# FrontEnd.net
KiCad netlist of a schematic drawn in EAGLE
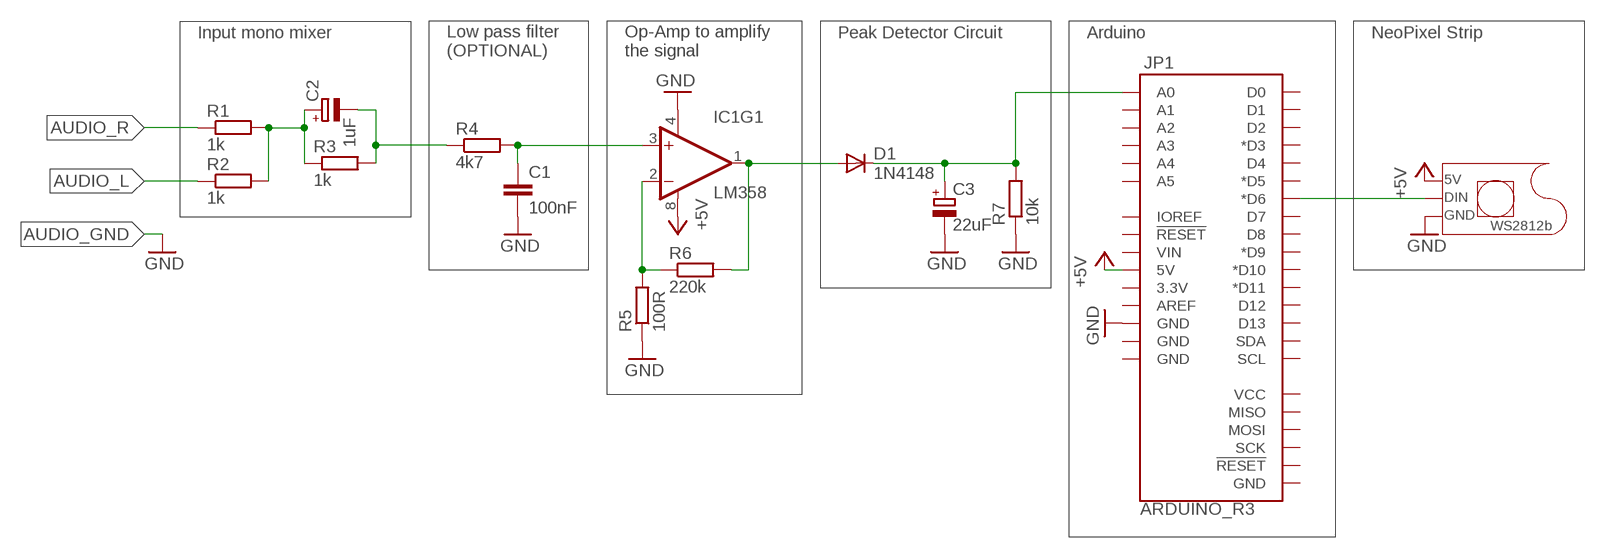
[diagram p0: schematic, sheet 1]

(export (version "E")
  (design (tool "Eeschema 10.0.6"))
  (components
    (comp (ref "C1")
      (value "100nF")
      (footprint "eagle-import:C025-024X044")
      (libsource (lib "eagle-import") (part "C-EU025-024X044"))
    )
    (comp (ref "C2")
      (value "1uF")
      (footprint "eagle-import:085CS_1AR")
      (libsource (lib "eagle-import") (part "CPOL-EU085CS-1AR"))
    )
    (comp (ref "C3")
      (value "22uF")
      (footprint "eagle-import:085CS_1AR")
      (libsource (lib "eagle-import") (part "CPOL-EU085CS-1AR"))
    )
    (comp (ref "D1")
      (value "1N4148")
      (footprint "eagle-import:DO35-10")
      (libsource (lib "eagle-import") (part "1N4148DO35-10"))
    )
    (comp (ref "IC1")
      (value "LM358")
      (footprint "eagle-import:DIP08")
      (libsource (lib "eagle-import") (part "LM358"))
    )
    (comp (ref "JP1")
      (value "ARDUINO_R3")
      (footprint "eagle-import:ARDUINO_R3")
      (libsource (lib "eagle-import") (part "ARDUINO_R3"))
    )
    (comp (ref "R1")
      (value "1k")
      (footprint "eagle-import:0204V")
      (libsource (lib "eagle-import") (part "R-EU_0204/2V"))
    )
    (comp (ref "R2")
      (value "1k")
      (footprint "eagle-import:0204V")
      (libsource (lib "eagle-import") (part "R-EU_0204/2V"))
    )
    (comp (ref "R3")
      (value "1k")
      (footprint "eagle-import:0204V")
      (libsource (lib "eagle-import") (part "R-EU_0204/2V"))
    )
    (comp (ref "R4")
      (value "4k7")
      (footprint "eagle-import:0204_5")
      (libsource (lib "eagle-import") (part "R-EU_0204/5"))
    )
    (comp (ref "R5")
      (value "100R")
      (footprint "eagle-import:0204V")
      (libsource (lib "eagle-import") (part "R-EU_0204/2V"))
    )
    (comp (ref "R6")
      (value "220k")
      (footprint "eagle-import:0204V")
      (libsource (lib "eagle-import") (part "R-EU_0204/2V"))
    )
    (comp (ref "R7")
      (value "10k")
      (footprint "eagle-import:0204V")
      (libsource (lib "eagle-import") (part "R-EU_0204/2V"))
    )
  )
  (nets
    (net (code "1") (name "+5V") (class "Default")
      (node (ref "IC1") (pin "8") (pinfunction "V+_8") (pintype "power_in"))
      (node (ref "JP1") (pin "5V") (pinfunction "5V_5V") (pintype "bidirectional"))
    )
    (net (code "2") (name "AUDIO_GND") (class "Default")
      (node (ref "C1") (pin "2") (pinfunction "2_2") (pintype "passive"))
      (node (ref "C3") (pin "-") (pinfunction "-_-") (pintype "passive"))
      (node (ref "IC1") (pin "4") (pinfunction "V-_4") (pintype "power_in"))
      (node (ref "JP1") (pin "GND@4") (pinfunction "GND_GND@4") (pintype "bidirectional"))
      (node (ref "R5") (pin "1") (pinfunction "1_1") (pintype "passive"))
      (node (ref "R7") (pin "1") (pinfunction "1_1") (pintype "passive"))
    )
    (net (code "3") (name "AUDIO_L") (class "Default")
      (node (ref "R2") (pin "1") (pinfunction "1_1") (pintype "passive"))
    )
    (net (code "4") (name "AUDIO_R") (class "Default")
      (node (ref "R1") (pin "1") (pinfunction "1_1") (pintype "passive"))
    )
    (net (code "5") (name "Net-(C2-Pad+)") (class "Default")
      (node (ref "C2") (pin "+") (pinfunction "+_+") (pintype "passive"))
      (node (ref "R1") (pin "2") (pinfunction "2_2") (pintype "passive"))
      (node (ref "R2") (pin "2") (pinfunction "2_2") (pintype "passive"))
      (node (ref "R3") (pin "1") (pinfunction "1_1") (pintype "passive"))
    )
    (net (code "6") (name "Net-(C2-Pad-)") (class "Default")
      (node (ref "C2") (pin "-") (pinfunction "-_-") (pintype "passive"))
      (node (ref "R3") (pin "2") (pinfunction "2_2") (pintype "passive"))
      (node (ref "R4") (pin "1") (pinfunction "1_1") (pintype "passive"))
    )
    (net (code "7") (name "Net-(C3-Pad+)") (class "Default")
      (node (ref "C3") (pin "+") (pinfunction "+_+") (pintype "passive"))
      (node (ref "D1") (pin "C") (pinfunction "C_C") (pintype "passive"))
      (node (ref "JP1") (pin "A0") (pinfunction "A0_A0") (pintype "bidirectional"))
      (node (ref "R7") (pin "2") (pinfunction "2_2") (pintype "passive"))
    )
    (net (code "8") (name "Net-(IC1A-+IN)") (class "Default")
      (node (ref "C1") (pin "1") (pinfunction "1_1") (pintype "passive"))
      (node (ref "IC1") (pin "3") (pinfunction "+IN_3") (pintype "input"))
      (node (ref "R4") (pin "2") (pinfunction "2_2") (pintype "passive"))
    )
    (net (code "9") (name "Net-(IC1A--IN)") (class "Default")
      (node (ref "IC1") (pin "2") (pinfunction "-IN_2") (pintype "input"))
      (node (ref "R5") (pin "2") (pinfunction "2_2") (pintype "passive"))
      (node (ref "R6") (pin "1") (pinfunction "1_1") (pintype "passive"))
    )
    (net (code "10") (name "Net-(IC1A-OUT)") (class "Default")
      (node (ref "D1") (pin "A") (pinfunction "A_A") (pintype "passive"))
      (node (ref "IC1") (pin "1") (pinfunction "OUT_1") (pintype "output"))
      (node (ref "R6") (pin "2") (pinfunction "2_2") (pintype "passive"))
    )
    (net (code "11") (name "unconnected-(JP1-*D3-PadD3)") (class "Default")
      (node (ref "JP1") (pin "D3") (pinfunction "*D3_D3") (pintype "bidirectional"))
    )
    (net (code "12") (name "unconnected-(JP1-*D5-PadD5)") (class "Default")
      (node (ref "JP1") (pin "D5") (pinfunction "*D5_D5") (pintype "bidirectional"))
    )
    (net (code "13") (name "unconnected-(JP1-*D6-PadD6)") (class "Default")
      (node (ref "JP1") (pin "D6") (pinfunction "*D6_D6") (pintype "bidirectional"))
    )
    (net (code "14") (name "unconnected-(JP1-*D9-PadD9)") (class "Default")
      (node (ref "JP1") (pin "D9") (pinfunction "*D9_D9") (pintype "bidirectional"))
    )
    (net (code "15") (name "unconnected-(JP1-*D10-PadD10)") (class "Default")
      (node (ref "JP1") (pin "D10") (pinfunction "*D10_D10") (pintype "bidirectional"))
    )
    (net (code "16") (name "unconnected-(JP1-*D11-PadD11)") (class "Default")
      (node (ref "JP1") (pin "D11") (pinfunction "*D11_D11") (pintype "bidirectional"))
    )
    (net (code "17") (name "unconnected-(JP1-GND-PadGND@1)") (class "Default")
      (node (ref "JP1") (pin "GND@1") (pinfunction "GND_GND@1") (pintype "bidirectional"))
    )
    (net (code "18") (name "unconnected-(JP1-GND-PadGND@2)") (class "Default")
      (node (ref "JP1") (pin "GND@2") (pinfunction "GND_GND@2") (pintype "bidirectional"))
    )
    (net (code "19") (name "unconnected-(JP1-GND-PadGND@3)") (class "Default")
      (node (ref "JP1") (pin "GND@3") (pinfunction "GND_GND@3") (pintype "bidirectional"))
    )
    (net (code "20") (name "unconnected-(JP1-Pad3.3V)") (class "Default")
      (node (ref "JP1") (pin "3.3V") (pinfunction "3.3V_3.3V") (pintype "bidirectional"))
    )
    (net (code "21") (name "unconnected-(JP1-PadA1)") (class "Default")
      (node (ref "JP1") (pin "A1") (pinfunction "A1_A1") (pintype "bidirectional"))
    )
    (net (code "22") (name "unconnected-(JP1-PadA2)") (class "Default")
      (node (ref "JP1") (pin "A2") (pinfunction "A2_A2") (pintype "bidirectional"))
    )
    (net (code "23") (name "unconnected-(JP1-PadA3)") (class "Default")
      (node (ref "JP1") (pin "A3") (pinfunction "A3_A3") (pintype "bidirectional"))
    )
    (net (code "24") (name "unconnected-(JP1-PadA4)") (class "Default")
      (node (ref "JP1") (pin "A4") (pinfunction "A4_A4") (pintype "bidirectional"))
    )
    (net (code "25") (name "unconnected-(JP1-PadA5)") (class "Default")
      (node (ref "JP1") (pin "A5") (pinfunction "A5_A5") (pintype "bidirectional"))
    )
    (net (code "26") (name "unconnected-(JP1-PadAREF)") (class "Default")
      (node (ref "JP1") (pin "AREF") (pinfunction "AREF_AREF") (pintype "bidirectional"))
    )
    (net (code "27") (name "unconnected-(JP1-PadD0)") (class "Default")
      (node (ref "JP1") (pin "D0") (pinfunction "D0_D0") (pintype "bidirectional"))
    )
    (net (code "28") (name "unconnected-(JP1-PadD1)") (class "Default")
      (node (ref "JP1") (pin "D1") (pinfunction "D1_D1") (pintype "bidirectional"))
    )
    (net (code "29") (name "unconnected-(JP1-PadD2)") (class "Default")
      (node (ref "JP1") (pin "D2") (pinfunction "D2_D2") (pintype "bidirectional"))
    )
    (net (code "30") (name "unconnected-(JP1-PadD4)") (class "Default")
      (node (ref "JP1") (pin "D4") (pinfunction "D4_D4") (pintype "bidirectional"))
    )
    (net (code "31") (name "unconnected-(JP1-PadD7)") (class "Default")
      (node (ref "JP1") (pin "D7") (pinfunction "D7_D7") (pintype "bidirectional"))
    )
    (net (code "32") (name "unconnected-(JP1-PadD8)") (class "Default")
      (node (ref "JP1") (pin "D8") (pinfunction "D8_D8") (pintype "bidirectional"))
    )
    (net (code "33") (name "unconnected-(JP1-PadD12)") (class "Default")
      (node (ref "JP1") (pin "D12") (pinfunction "D12_D12") (pintype "bidirectional"))
    )
    (net (code "34") (name "unconnected-(JP1-PadD13)") (class "Default")
      (node (ref "JP1") (pin "D13") (pinfunction "D13_D13") (pintype "bidirectional"))
    )
    (net (code "35") (name "unconnected-(JP1-PadIOREF)") (class "Default")
      (node (ref "JP1") (pin "IOREF") (pinfunction "IOREF_IOREF") (pintype "bidirectional"))
    )
    (net (code "36") (name "unconnected-(JP1-PadMISO)") (class "Default")
      (node (ref "JP1") (pin "MISO") (pinfunction "MISO_MISO") (pintype "bidirectional"))
    )
    (net (code "37") (name "unconnected-(JP1-PadMOSI)") (class "Default")
      (node (ref "JP1") (pin "MOSI") (pinfunction "MOSI_MOSI") (pintype "bidirectional"))
    )
    (net (code "38") (name "unconnected-(JP1-PadSCK)") (class "Default")
      (node (ref "JP1") (pin "SCK") (pinfunction "SCK_SCK") (pintype "bidirectional"))
    )
    (net (code "39") (name "unconnected-(JP1-PadSCL)") (class "Default")
      (node (ref "JP1") (pin "SCL") (pinfunction "SCL_SCL") (pintype "bidirectional"))
    )
    (net (code "40") (name "unconnected-(JP1-PadSDA)") (class "Default")
      (node (ref "JP1") (pin "SDA") (pinfunction "SDA_SDA") (pintype "bidirectional"))
    )
    (net (code "41") (name "unconnected-(JP1-PadVCC)") (class "Default")
      (node (ref "JP1") (pin "VCC") (pinfunction "VCC_VCC") (pintype "bidirectional"))
    )
    (net (code "42") (name "unconnected-(JP1-PadVIN)") (class "Default")
      (node (ref "JP1") (pin "VIN") (pinfunction "VIN_VIN") (pintype "bidirectional"))
    )
    (net (code "43") (name "unconnected-(JP1-~{RESET}-PadRESET@1)") (class "Default")
      (node (ref "JP1") (pin "RESET@1") (pinfunction "~{RESET}_RESET@1") (pintype "bidirectional"))
    )
    (net (code "44") (name "unconnected-(JP1-~{RESET}-PadRESET@2)") (class "Default")
      (node (ref "JP1") (pin "RESET@2") (pinfunction "~{RESET}_RESET@2") (pintype "bidirectional"))
    )
  )
)
